# MotorDriver.net
KiCad netlist of a schematic drawn in EAGLE
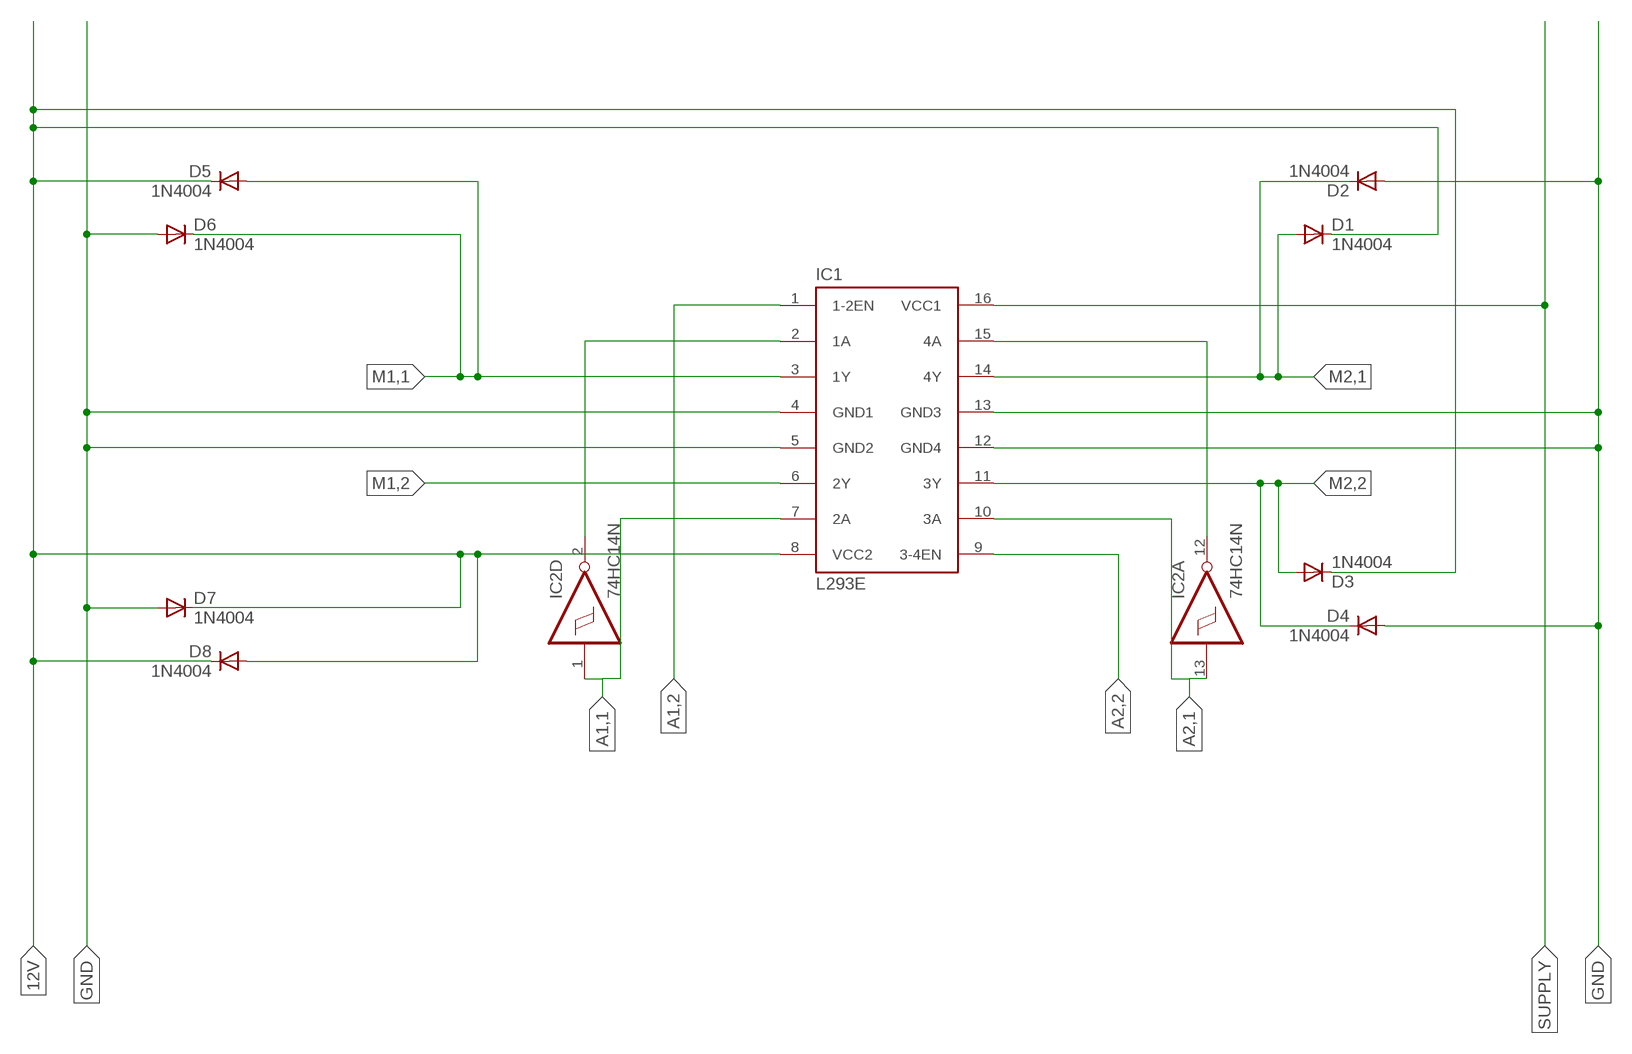
[diagram p0: schematic, sheet 1]

(export (version "E")
  (design (tool "Eeschema 10.0.6"))
  (components
    (comp (ref "D1")
      (value "1N4004")
      (footprint "eagle-import:DO41-10")
      (libsource (lib "eagle-import") (part "1N4004"))
    )
    (comp (ref "D2")
      (value "1N4004")
      (footprint "eagle-import:DO41-10")
      (libsource (lib "eagle-import") (part "1N4004"))
    )
    (comp (ref "D3")
      (value "1N4004")
      (footprint "eagle-import:DO41-10")
      (libsource (lib "eagle-import") (part "1N4004"))
    )
    (comp (ref "D4")
      (value "1N4004")
      (footprint "eagle-import:DO41-10")
      (libsource (lib "eagle-import") (part "1N4004"))
    )
    (comp (ref "D5")
      (value "1N4004")
      (footprint "eagle-import:DO41-10")
      (libsource (lib "eagle-import") (part "1N4004"))
    )
    (comp (ref "D6")
      (value "1N4004")
      (footprint "eagle-import:DO41-10")
      (libsource (lib "eagle-import") (part "1N4004"))
    )
    (comp (ref "D7")
      (value "1N4004")
      (footprint "eagle-import:DO41-10")
      (libsource (lib "eagle-import") (part "1N4004"))
    )
    (comp (ref "D8")
      (value "1N4004")
      (footprint "eagle-import:DO41-10")
      (libsource (lib "eagle-import") (part "1N4004"))
    )
    (comp (ref "IC1")
      (value "L293E")
      (footprint "eagle-import:DIL16")
      (fields (field (name "MF") "Arrow Electronics"))
      (libsource (lib "eagle-import") (part "L293E"))
    )
    (comp (ref "IC2")
      (value "74HC14N")
      (footprint "eagle-import:DIL14")
      (libsource (lib "eagle-import") (part "7414NHC"))
    )
  )
  (nets
    (net (code "1") (name "12V") (class "Default")
      (node (ref "D1") (pin "C") (pinfunction "C_C") (pintype "passive"))
      (node (ref "D3") (pin "C") (pinfunction "C_C") (pintype "passive"))
      (node (ref "D5") (pin "C") (pinfunction "C_C") (pintype "passive"))
      (node (ref "D7") (pin "C") (pinfunction "C_C") (pintype "passive"))
      (node (ref "D8") (pin "A") (pinfunction "A_A") (pintype "passive"))
      (node (ref "D8") (pin "C") (pinfunction "C_C") (pintype "passive"))
      (node (ref "IC1") (pin "8") (pinfunction "VCC2_8") (pintype "power_in"))
    )
    (net (code "2") (name "A1,1") (class "Default")
      (node (ref "IC1") (pin "7") (pinfunction "2A_7") (pintype "input"))
      (node (ref "IC2") (pin "1") (pinfunction "I_1") (pintype "input"))
    )
    (net (code "3") (name "A1,2") (class "Default")
      (node (ref "IC1") (pin "1") (pinfunction "1-2EN_1") (pintype "input"))
    )
    (net (code "4") (name "A2,1") (class "Default")
      (node (ref "IC1") (pin "10") (pinfunction "3A_10") (pintype "input"))
      (node (ref "IC2") (pin "13") (pinfunction "I_13") (pintype "input"))
    )
    (net (code "5") (name "A2,2") (class "Default")
      (node (ref "IC1") (pin "9") (pinfunction "3-4EN_9") (pintype "input"))
    )
    (net (code "6") (name "GND") (class "Default")
      (node (ref "D2") (pin "A") (pinfunction "A_A") (pintype "passive"))
      (node (ref "D4") (pin "A") (pinfunction "A_A") (pintype "passive"))
      (node (ref "D6") (pin "A") (pinfunction "A_A") (pintype "passive"))
      (node (ref "D7") (pin "A") (pinfunction "A_A") (pintype "passive"))
      (node (ref "IC1") (pin "12") (pinfunction "GND4_12") (pintype "power_in"))
      (node (ref "IC1") (pin "13") (pinfunction "GND3_13") (pintype "power_in"))
      (node (ref "IC1") (pin "4") (pinfunction "GND1_4") (pintype "power_in"))
      (node (ref "IC1") (pin "5") (pinfunction "GND2_5") (pintype "power_in"))
    )
    (net (code "7") (name "M1,1") (class "Default")
      (node (ref "D5") (pin "A") (pinfunction "A_A") (pintype "passive"))
      (node (ref "D6") (pin "C") (pinfunction "C_C") (pintype "passive"))
      (node (ref "IC1") (pin "3") (pinfunction "1Y_3") (pintype "output"))
    )
    (net (code "8") (name "M1,2") (class "Default")
      (node (ref "IC1") (pin "6") (pinfunction "2Y_6") (pintype "output"))
    )
    (net (code "9") (name "M2,1") (class "Default")
      (node (ref "D1") (pin "A") (pinfunction "A_A") (pintype "passive"))
      (node (ref "D2") (pin "C") (pinfunction "C_C") (pintype "passive"))
      (node (ref "IC1") (pin "14") (pinfunction "4Y_14") (pintype "output"))
    )
    (net (code "10") (name "M2,2") (class "Default")
      (node (ref "D3") (pin "A") (pinfunction "A_A") (pintype "passive"))
      (node (ref "D4") (pin "C") (pinfunction "C_C") (pintype "passive"))
      (node (ref "IC1") (pin "11") (pinfunction "3Y_11") (pintype "output"))
    )
    (net (code "11") (name "Net-(IC1-1A)") (class "Default")
      (node (ref "IC1") (pin "2") (pinfunction "1A_2") (pintype "input"))
      (node (ref "IC2") (pin "2") (pinfunction "O_2") (pintype "output"))
    )
    (net (code "12") (name "Net-(IC1-4A)") (class "Default")
      (node (ref "IC1") (pin "15") (pinfunction "4A_15") (pintype "input"))
      (node (ref "IC2") (pin "12") (pinfunction "O_12") (pintype "output"))
    )
    (net (code "13") (name "SUPPLY") (class "Default")
      (node (ref "IC1") (pin "16") (pinfunction "VCC1_16") (pintype "power_in"))
    )
  )
)
